# TonESP.net
KiCad netlist of a schematic drawn in EAGLE
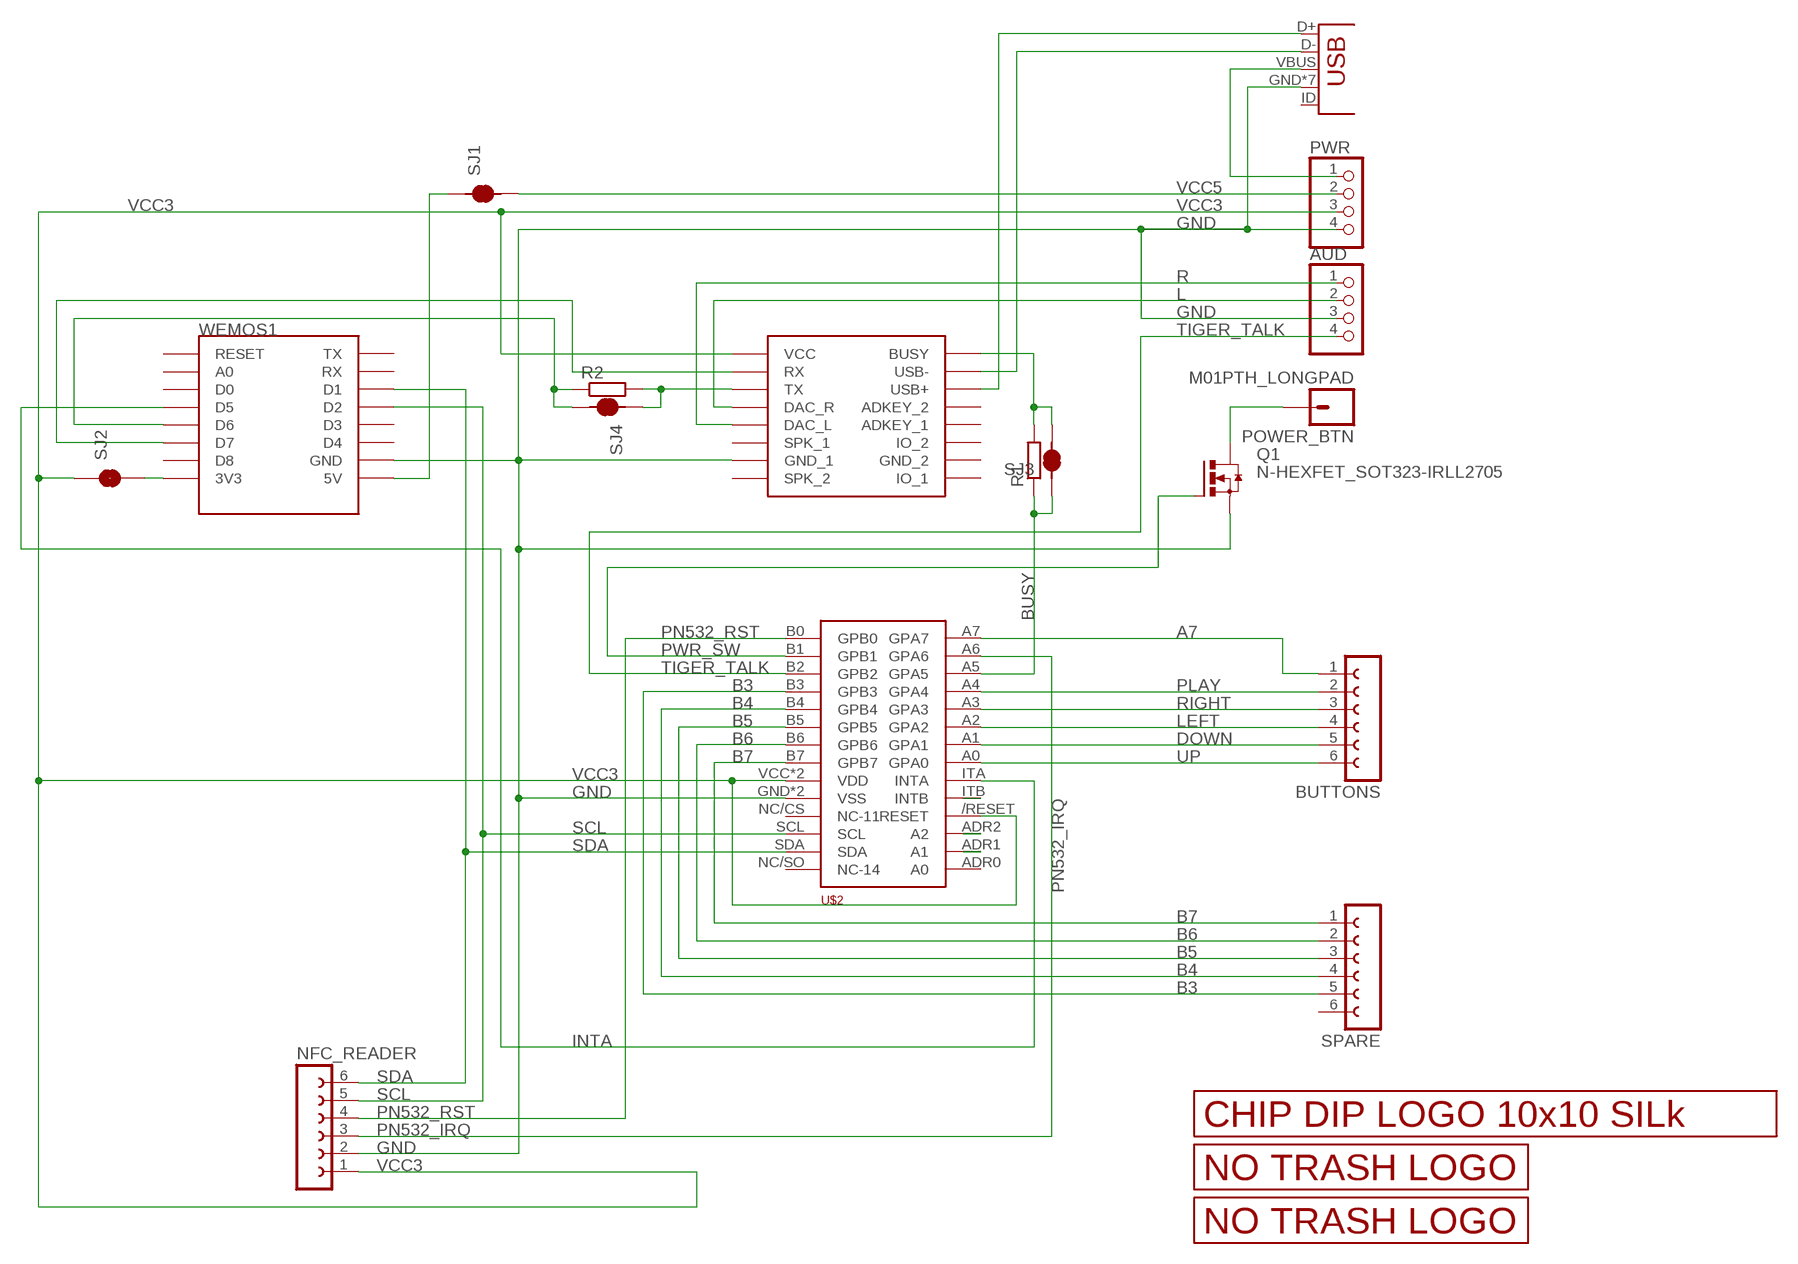
[diagram p0: schematic, sheet 1]

(export (version "E")
  (design (tool "Eeschema 10.0.6"))
  (components
    (comp (ref "AUD")
      (value "PINHD-1X4")
      (footprint "eagle-import:1X04")
      (libsource (lib "eagle-import") (part "PINHD-1X4"))
    )
    (comp (ref "BUTTONS")
      (value "FE06-1")
      (footprint "eagle-import:FE06")
      (libsource (lib "eagle-import") (part "FE06-1"))
    )
    (comp (ref "JP1")
      (value "USBUSB-MICROB-SMT-DIP")
      (footprint "eagle-import:USB-MICROB-SMT-DIP")
      (libsource (lib "eagle-import") (part "USBUSB-MICROB-SMT-DIP"))
    )
    (comp (ref "NFC_READER")
      (value "FE06-1")
      (footprint "eagle-import:FE06")
      (libsource (lib "eagle-import") (part "FE06-1"))
    )
    (comp (ref "POWER_BTN")
      (value "M01PTH_LONGPAD")
      (footprint "eagle-import:1X01_LONGPAD")
      (libsource (lib "eagle-import") (part "M01PTH_LONGPAD"))
    )
    (comp (ref "PWR")
      (value "PINHD-1X4")
      (footprint "eagle-import:1X04")
      (libsource (lib "eagle-import") (part "PINHD-1X4"))
    )
    (comp (ref "Q1")
      (value "N-HEXFET_SOT323-IRLL2705")
      (footprint "eagle-import:SOT223")
      (libsource (lib "eagle-import") (part "N-HEXFET_?-SOT323IRLL2705"))
    )
    (comp (ref "R1")
      (value "R-EU_M0805")
      (footprint "eagle-import:M0805")
      (libsource (lib "eagle-import") (part "R-EU_M0805"))
    )
    (comp (ref "R2")
      (value "R-EU_M0805")
      (footprint "eagle-import:M0805")
      (libsource (lib "eagle-import") (part "R-EU_M0805"))
    )
    (comp (ref "SJ1")
      (value "SMD_SJ_2WAY_CLOSEDCLOSED")
      (footprint "eagle-import:SMD_SJ_2WAY_CLOSED")
      (libsource (lib "eagle-import") (part "SMD_SJ_2WAY_CLOSEDCLOSED"))
    )
    (comp (ref "SJ2")
      (value "SMD_SJ_2WAY_OPEN")
      (footprint "eagle-import:SMD_SJ_2WAY_OPEN")
      (libsource (lib "eagle-import") (part "SMD_SJ_2WAY_OPEN"))
    )
    (comp (ref "SJ3")
      (value "SMD_SJ_2WAY_CLOSEDCLOSED")
      (footprint "eagle-import:SMD_SJ_2WAY_CLOSED")
      (libsource (lib "eagle-import") (part "SMD_SJ_2WAY_CLOSEDCLOSED"))
    )
    (comp (ref "SJ4")
      (value "SMD_SJ_2WAY_CLOSEDCLOSED")
      (footprint "eagle-import:SMD_SJ_2WAY_CLOSED")
      (libsource (lib "eagle-import") (part "SMD_SJ_2WAY_CLOSEDCLOSED"))
    )
    (comp (ref "SPARE")
      (value "FE06-1")
      (footprint "eagle-import:FE06")
      (libsource (lib "eagle-import") (part "FE06-1"))
    )
    (comp (ref "U$1")
      (value "DFPLAYER")
      (footprint "eagle-import:DFPLAYER")
      (libsource (lib "eagle-import") (part "DFPLAYER"))
    )
    (comp (ref "U$2")
      (value "MCP23017-E/SP")
      (footprint "eagle-import:MODULE")
      (libsource (lib "eagle-import") (part "MCP23017-E/SP"))
    )
    (comp (ref "U$4")
      (value "LOGO_10X10_SILK")
      (footprint "eagle-import:LOGO2_10X10_SILK")
      (libsource (lib "eagle-import") (part "LOGO_10X10_SILK"))
    )
    (comp (ref "U$5")
      (value "LOGO_NO_TRASHNO_TRASH")
      (footprint "eagle-import:LOGO_ROHS_NO_TRASH")
      (libsource (lib "eagle-import") (part "LOGO_NO_TRASHNO_TRASH"))
    )
    (comp (ref "U$6")
      (value "LOGO_NO_TRASHROHS")
      (footprint "eagle-import:LOGO_ROHS_SYM")
      (libsource (lib "eagle-import") (part "LOGO_NO_TRASHROHS"))
    )
    (comp (ref "WEMOS1")
      (value "WEMOS-D1-MINITXT")
      (footprint "eagle-import:WEMOS-D1-MINI")
      (libsource (lib "eagle-import") (part "WEMOS-D1-MINITXT"))
    )
  )
  (nets
    (net (code "1") (name "/A7") (class "Default")
      (node (ref "BUTTONS") (pin "1") (pinfunction "1_1") (pintype "passive"))
      (node (ref "U$2") (pin "A7") (pinfunction "GPA7_A7") (pintype "bidirectional"))
    )
    (net (code "2") (name "/B3") (class "Default")
      (node (ref "SPARE") (pin "5") (pinfunction "5_5") (pintype "passive"))
      (node (ref "U$2") (pin "B3") (pinfunction "GPB3_B3") (pintype "bidirectional"))
    )
    (net (code "3") (name "/B4") (class "Default")
      (node (ref "SPARE") (pin "4") (pinfunction "4_4") (pintype "passive"))
      (node (ref "U$2") (pin "B4") (pinfunction "GPB4_B4") (pintype "bidirectional"))
    )
    (net (code "4") (name "/B5") (class "Default")
      (node (ref "SPARE") (pin "3") (pinfunction "3_3") (pintype "passive"))
      (node (ref "U$2") (pin "B5") (pinfunction "GPB5_B5") (pintype "bidirectional"))
    )
    (net (code "5") (name "/B6") (class "Default")
      (node (ref "SPARE") (pin "2") (pinfunction "2_2") (pintype "passive"))
      (node (ref "U$2") (pin "B6") (pinfunction "GPB6_B6") (pintype "bidirectional"))
    )
    (net (code "6") (name "/B7") (class "Default")
      (node (ref "SPARE") (pin "1") (pinfunction "1_1") (pintype "passive"))
      (node (ref "U$2") (pin "B7") (pinfunction "GPB7_B7") (pintype "bidirectional"))
    )
    (net (code "7") (name "/BUSY") (class "Default")
      (node (ref "R1") (pin "1") (pinfunction "1_1") (pintype "passive"))
      (node (ref "SJ3") (pin "1") (pinfunction "1_1") (pintype "passive"))
      (node (ref "U$2") (pin "A5") (pinfunction "GPA5_A5") (pintype "bidirectional"))
    )
    (net (code "8") (name "/DOWN") (class "Default")
      (node (ref "BUTTONS") (pin "5") (pinfunction "5_5") (pintype "passive"))
      (node (ref "U$2") (pin "A1") (pinfunction "GPA1_A1") (pintype "bidirectional"))
    )
    (net (code "9") (name "/GND") (class "Default")
      (node (ref "AUD") (pin "3") (pinfunction "3_3") (pintype "passive"))
      (node (ref "JP1") (pin "GND") (pinfunction "GND_GND") (pintype "bidirectional"))
      (node (ref "JP1") (pin "MT1") (pinfunction "GND_MT1") (pintype "bidirectional"))
      (node (ref "JP1") (pin "MT2") (pinfunction "GND_MT2") (pintype "bidirectional"))
      (node (ref "JP1") (pin "MT3") (pinfunction "GND_MT3") (pintype "bidirectional"))
      (node (ref "JP1") (pin "MT4") (pinfunction "GND_MT4") (pintype "bidirectional"))
      (node (ref "JP1") (pin "P$1") (pinfunction "GND_P$1") (pintype "bidirectional"))
      (node (ref "JP1") (pin "P$2") (pinfunction "GND_P$2") (pintype "bidirectional"))
      (node (ref "NFC_READER") (pin "2") (pinfunction "2_2") (pintype "passive"))
      (node (ref "PWR") (pin "4") (pinfunction "4_4") (pintype "passive"))
      (node (ref "Q1") (pin "3") (pinfunction "S_3") (pintype "passive"))
      (node (ref "U$1") (pin "GND_1") (pinfunction "GND_1_GND_1") (pintype "bidirectional"))
      (node (ref "U$2") (pin "GND") (pinfunction "VSS_GND") (pintype "bidirectional"))
      (node (ref "U$2") (pin "GND2") (pinfunction "VSS_GND2") (pintype "bidirectional"))
      (node (ref "WEMOS1") (pin "GND") (pinfunction "GND_GND") (pintype "bidirectional"))
    )
    (net (code "10") (name "/INTA") (class "Default")
      (node (ref "U$2") (pin "ITA") (pinfunction "INTA_ITA") (pintype "bidirectional"))
      (node (ref "WEMOS1") (pin "D5") (pinfunction "D5_D5") (pintype "bidirectional"))
    )
    (net (code "11") (name "/L") (class "Default")
      (node (ref "AUD") (pin "2") (pinfunction "2_2") (pintype "passive"))
      (node (ref "U$1") (pin "DAC_R") (pinfunction "DAC_R_DAC_R") (pintype "bidirectional"))
    )
    (net (code "12") (name "/LEFT") (class "Default")
      (node (ref "BUTTONS") (pin "4") (pinfunction "4_4") (pintype "passive"))
      (node (ref "U$2") (pin "A2") (pinfunction "GPA2_A2") (pintype "bidirectional"))
    )
    (net (code "13") (name "/PLAY") (class "Default")
      (node (ref "BUTTONS") (pin "2") (pinfunction "2_2") (pintype "passive"))
      (node (ref "U$2") (pin "A4") (pinfunction "GPA4_A4") (pintype "bidirectional"))
    )
    (net (code "14") (name "/PN532_IRQ") (class "Default")
      (node (ref "NFC_READER") (pin "3") (pinfunction "3_3") (pintype "passive"))
      (node (ref "U$2") (pin "A6") (pinfunction "GPA6_A6") (pintype "bidirectional"))
    )
    (net (code "15") (name "/PN532_RST") (class "Default")
      (node (ref "NFC_READER") (pin "4") (pinfunction "4_4") (pintype "passive"))
      (node (ref "U$2") (pin "B0") (pinfunction "GPB0_B0") (pintype "bidirectional"))
    )
    (net (code "16") (name "/PWR_SW") (class "Default")
      (node (ref "Q1") (pin "1") (pinfunction "G_1") (pintype "passive"))
      (node (ref "U$2") (pin "B1") (pinfunction "GPB1_B1") (pintype "bidirectional"))
    )
    (net (code "17") (name "/R") (class "Default")
      (node (ref "AUD") (pin "1") (pinfunction "1_1") (pintype "passive"))
      (node (ref "U$1") (pin "DAC_L") (pinfunction "DAC_L_DAC_L") (pintype "bidirectional"))
    )
    (net (code "18") (name "/RIGHT") (class "Default")
      (node (ref "BUTTONS") (pin "3") (pinfunction "3_3") (pintype "passive"))
      (node (ref "U$2") (pin "A3") (pinfunction "GPA3_A3") (pintype "bidirectional"))
    )
    (net (code "19") (name "/SCL") (class "Default")
      (node (ref "NFC_READER") (pin "5") (pinfunction "5_5") (pintype "passive"))
      (node (ref "U$2") (pin "SCL") (pinfunction "SCL_SCL") (pintype "bidirectional"))
      (node (ref "WEMOS1") (pin "D2") (pinfunction "D2_D2") (pintype "bidirectional"))
    )
    (net (code "20") (name "/SDA") (class "Default")
      (node (ref "NFC_READER") (pin "6") (pinfunction "6_6") (pintype "passive"))
      (node (ref "U$2") (pin "SDA") (pinfunction "SDA_SDA") (pintype "bidirectional"))
      (node (ref "WEMOS1") (pin "D1") (pinfunction "D1_D1") (pintype "bidirectional"))
    )
    (net (code "21") (name "/TIGER_TALK") (class "Default")
      (node (ref "AUD") (pin "4") (pinfunction "4_4") (pintype "passive"))
      (node (ref "U$2") (pin "B2") (pinfunction "GPB2_B2") (pintype "bidirectional"))
    )
    (net (code "22") (name "/UP") (class "Default")
      (node (ref "BUTTONS") (pin "6") (pinfunction "6_6") (pintype "passive"))
      (node (ref "U$2") (pin "A0") (pinfunction "GPA0_A0") (pintype "bidirectional"))
    )
    (net (code "23") (name "/VCC3") (class "Default")
      (node (ref "NFC_READER") (pin "1") (pinfunction "1_1") (pintype "passive"))
      (node (ref "PWR") (pin "3") (pinfunction "3_3") (pintype "passive"))
      (node (ref "SJ2") (pin "1") (pinfunction "1_1") (pintype "passive"))
      (node (ref "U$1") (pin "VCC") (pinfunction "VCC_VCC") (pintype "bidirectional"))
      (node (ref "U$2") (pin "/RESET") (pinfunction "RESET_/RESET") (pintype "bidirectional"))
      (node (ref "U$2") (pin "VCC") (pinfunction "VDD_VCC") (pintype "bidirectional"))
      (node (ref "U$2") (pin "VCC2") (pinfunction "VDD_VCC2") (pintype "bidirectional"))
    )
    (net (code "24") (name "/VCC5") (class "Default")
      (node (ref "PWR") (pin "2") (pinfunction "2_2") (pintype "passive"))
      (node (ref "SJ1") (pin "3") (pinfunction "3_3") (pintype "passive"))
    )
    (net (code "25") (name "Net-(JP1-PadD+)") (class "Default")
      (node (ref "JP1") (pin "D+") (pinfunction "D+_D+") (pintype "bidirectional"))
      (node (ref "U$1") (pin "USB+") (pinfunction "USB+_USB+") (pintype "bidirectional"))
    )
    (net (code "26") (name "Net-(JP1-PadD-)") (class "Default")
      (node (ref "JP1") (pin "D-") (pinfunction "D-_D-") (pintype "bidirectional"))
      (node (ref "U$1") (pin "USB-") (pinfunction "USB-_USB-") (pintype "bidirectional"))
    )
    (net (code "27") (name "Net-(JP1-PadVBUS)") (class "Default")
      (node (ref "JP1") (pin "VBUS") (pinfunction "VBUS_VBUS") (pintype "bidirectional"))
      (node (ref "PWR") (pin "1") (pinfunction "1_1") (pintype "passive"))
    )
    (net (code "28") (name "Net-(Q1-D)") (class "Default")
      (node (ref "POWER_BTN") (pin "1") (pinfunction "1_1") (pintype "passive"))
      (node (ref "Q1") (pin "4") (pinfunction "D_4") (pintype "passive"))
    )
    (net (code "29") (name "Net-(R1-Pad2)") (class "Default")
      (node (ref "R1") (pin "2") (pinfunction "2_2") (pintype "passive"))
      (node (ref "SJ3") (pin "3") (pinfunction "3_3") (pintype "passive"))
      (node (ref "U$1") (pin "BUSY") (pinfunction "BUSY_BUSY") (pintype "bidirectional"))
    )
    (net (code "30") (name "Net-(R2-Pad1)") (class "Default")
      (node (ref "R2") (pin "1") (pinfunction "1_1") (pintype "passive"))
      (node (ref "SJ4") (pin "3") (pinfunction "3_3") (pintype "passive"))
      (node (ref "WEMOS1") (pin "D6") (pinfunction "D6_D6") (pintype "bidirectional"))
    )
    (net (code "31") (name "Net-(R2-Pad2)") (class "Default")
      (node (ref "R2") (pin "2") (pinfunction "2_2") (pintype "passive"))
      (node (ref "SJ4") (pin "1") (pinfunction "1_1") (pintype "passive"))
      (node (ref "U$1") (pin "TX") (pinfunction "TX_TX") (pintype "bidirectional"))
    )
    (net (code "32") (name "Net-(SJ1-Pad1)") (class "Default")
      (node (ref "SJ1") (pin "1") (pinfunction "1_1") (pintype "passive"))
      (node (ref "WEMOS1") (pin "5V") (pinfunction "5V_5V") (pintype "bidirectional"))
    )
    (net (code "33") (name "Net-(SJ2-Pad3)") (class "Default")
      (node (ref "SJ2") (pin "3") (pinfunction "3_3") (pintype "passive"))
      (node (ref "WEMOS1") (pin "3V3") (pinfunction "3V3_3V3") (pintype "bidirectional"))
    )
    (net (code "34") (name "Net-(U$1-PadRX)") (class "Default")
      (node (ref "U$1") (pin "RX") (pinfunction "RX_RX") (pintype "bidirectional"))
      (node (ref "WEMOS1") (pin "D7") (pinfunction "D7_D7") (pintype "bidirectional"))
    )
    (net (code "35") (name "unconnected-(JP1-PadID)") (class "Default")
      (node (ref "JP1") (pin "ID") (pinfunction "ID_ID") (pintype "bidirectional"))
    )
    (net (code "36") (name "unconnected-(SPARE-Pad6)") (class "Default")
      (node (ref "SPARE") (pin "6") (pinfunction "6_6") (pintype "passive"))
    )
    (net (code "37") (name "unconnected-(U$1-ADKEY_1-PadADKEY1)") (class "Default")
      (node (ref "U$1") (pin "ADKEY1") (pinfunction "ADKEY_1_ADKEY1") (pintype "bidirectional"))
    )
    (net (code "38") (name "unconnected-(U$1-ADKEY_2-PadADKEY2)") (class "Default")
      (node (ref "U$1") (pin "ADKEY2") (pinfunction "ADKEY_2_ADKEY2") (pintype "bidirectional"))
    )
    (net (code "39") (name "unconnected-(U$1-IO_1-PadIO1)") (class "Default")
      (node (ref "U$1") (pin "IO1") (pinfunction "IO_1_IO1") (pintype "bidirectional"))
    )
    (net (code "40") (name "unconnected-(U$1-IO_2-PadIO2)") (class "Default")
      (node (ref "U$1") (pin "IO2") (pinfunction "IO_2_IO2") (pintype "bidirectional"))
    )
    (net (code "41") (name "unconnected-(U$1-PadGND_2)") (class "Default")
      (node (ref "U$1") (pin "GND_2") (pinfunction "GND_2_GND_2") (pintype "bidirectional"))
    )
    (net (code "42") (name "unconnected-(U$1-SPK_1-PadSPK1)") (class "Default")
      (node (ref "U$1") (pin "SPK1") (pinfunction "SPK_1_SPK1") (pintype "bidirectional"))
    )
    (net (code "43") (name "unconnected-(U$1-SPK_2-PadSPK2)") (class "Default")
      (node (ref "U$1") (pin "SPK2") (pinfunction "SPK_2_SPK2") (pintype "bidirectional"))
    )
    (net (code "44") (name "unconnected-(U$2-A0-PadADR0)") (class "Default")
      (node (ref "U$2") (pin "ADR0") (pinfunction "A0_ADR0") (pintype "bidirectional"))
    )
    (net (code "45") (name "unconnected-(U$2-A1-PadADR1)") (class "Default")
      (node (ref "U$2") (pin "ADR1") (pinfunction "A1_ADR1") (pintype "bidirectional"))
    )
    (net (code "46") (name "unconnected-(U$2-A2-PadADR2)") (class "Default")
      (node (ref "U$2") (pin "ADR2") (pinfunction "A2_ADR2") (pintype "bidirectional"))
    )
    (net (code "47") (name "unconnected-(U$2-INTB-PadITB)") (class "Default")
      (node (ref "U$2") (pin "ITB") (pinfunction "INTB_ITB") (pintype "bidirectional"))
    )
    (net (code "48") (name "unconnected-(U$2-NC-11-PadNC{slash}CS)") (class "Default")
      (node (ref "U$2") (pin "NC/CS") (pinfunction "NC-11_NC/CS") (pintype "bidirectional"))
    )
    (net (code "49") (name "unconnected-(U$2-NC-14-PadNC{slash}SO)") (class "Default")
      (node (ref "U$2") (pin "NC/SO") (pinfunction "NC-14_NC/SO") (pintype "bidirectional"))
    )
    (net (code "50") (name "unconnected-(WEMOS1-PadA0)") (class "Default")
      (node (ref "WEMOS1") (pin "A0") (pinfunction "A0_A0") (pintype "bidirectional"))
    )
    (net (code "51") (name "unconnected-(WEMOS1-PadD0)") (class "Default")
      (node (ref "WEMOS1") (pin "D0") (pinfunction "D0_D0") (pintype "bidirectional"))
    )
    (net (code "52") (name "unconnected-(WEMOS1-PadD3)") (class "Default")
      (node (ref "WEMOS1") (pin "D3") (pinfunction "D3_D3") (pintype "bidirectional"))
    )
    (net (code "53") (name "unconnected-(WEMOS1-PadD4)") (class "Default")
      (node (ref "WEMOS1") (pin "D4") (pinfunction "D4_D4") (pintype "bidirectional"))
    )
    (net (code "54") (name "unconnected-(WEMOS1-PadD8)") (class "Default")
      (node (ref "WEMOS1") (pin "D8") (pinfunction "D8_D8") (pintype "bidirectional"))
    )
    (net (code "55") (name "unconnected-(WEMOS1-PadRESET)") (class "Default")
      (node (ref "WEMOS1") (pin "RESET") (pinfunction "RESET_RESET") (pintype "bidirectional"))
    )
    (net (code "56") (name "unconnected-(WEMOS1-PadRX)") (class "Default")
      (node (ref "WEMOS1") (pin "RX") (pinfunction "RX_RX") (pintype "bidirectional"))
    )
    (net (code "57") (name "unconnected-(WEMOS1-PadTX)") (class "Default")
      (node (ref "WEMOS1") (pin "TX") (pinfunction "TX_TX") (pintype "bidirectional"))
    )
  )
)
